# SCH_WL-134A-Carrier-Board_2025-03-29.net
KiCad netlist of a schematic drawn in EasyEDA
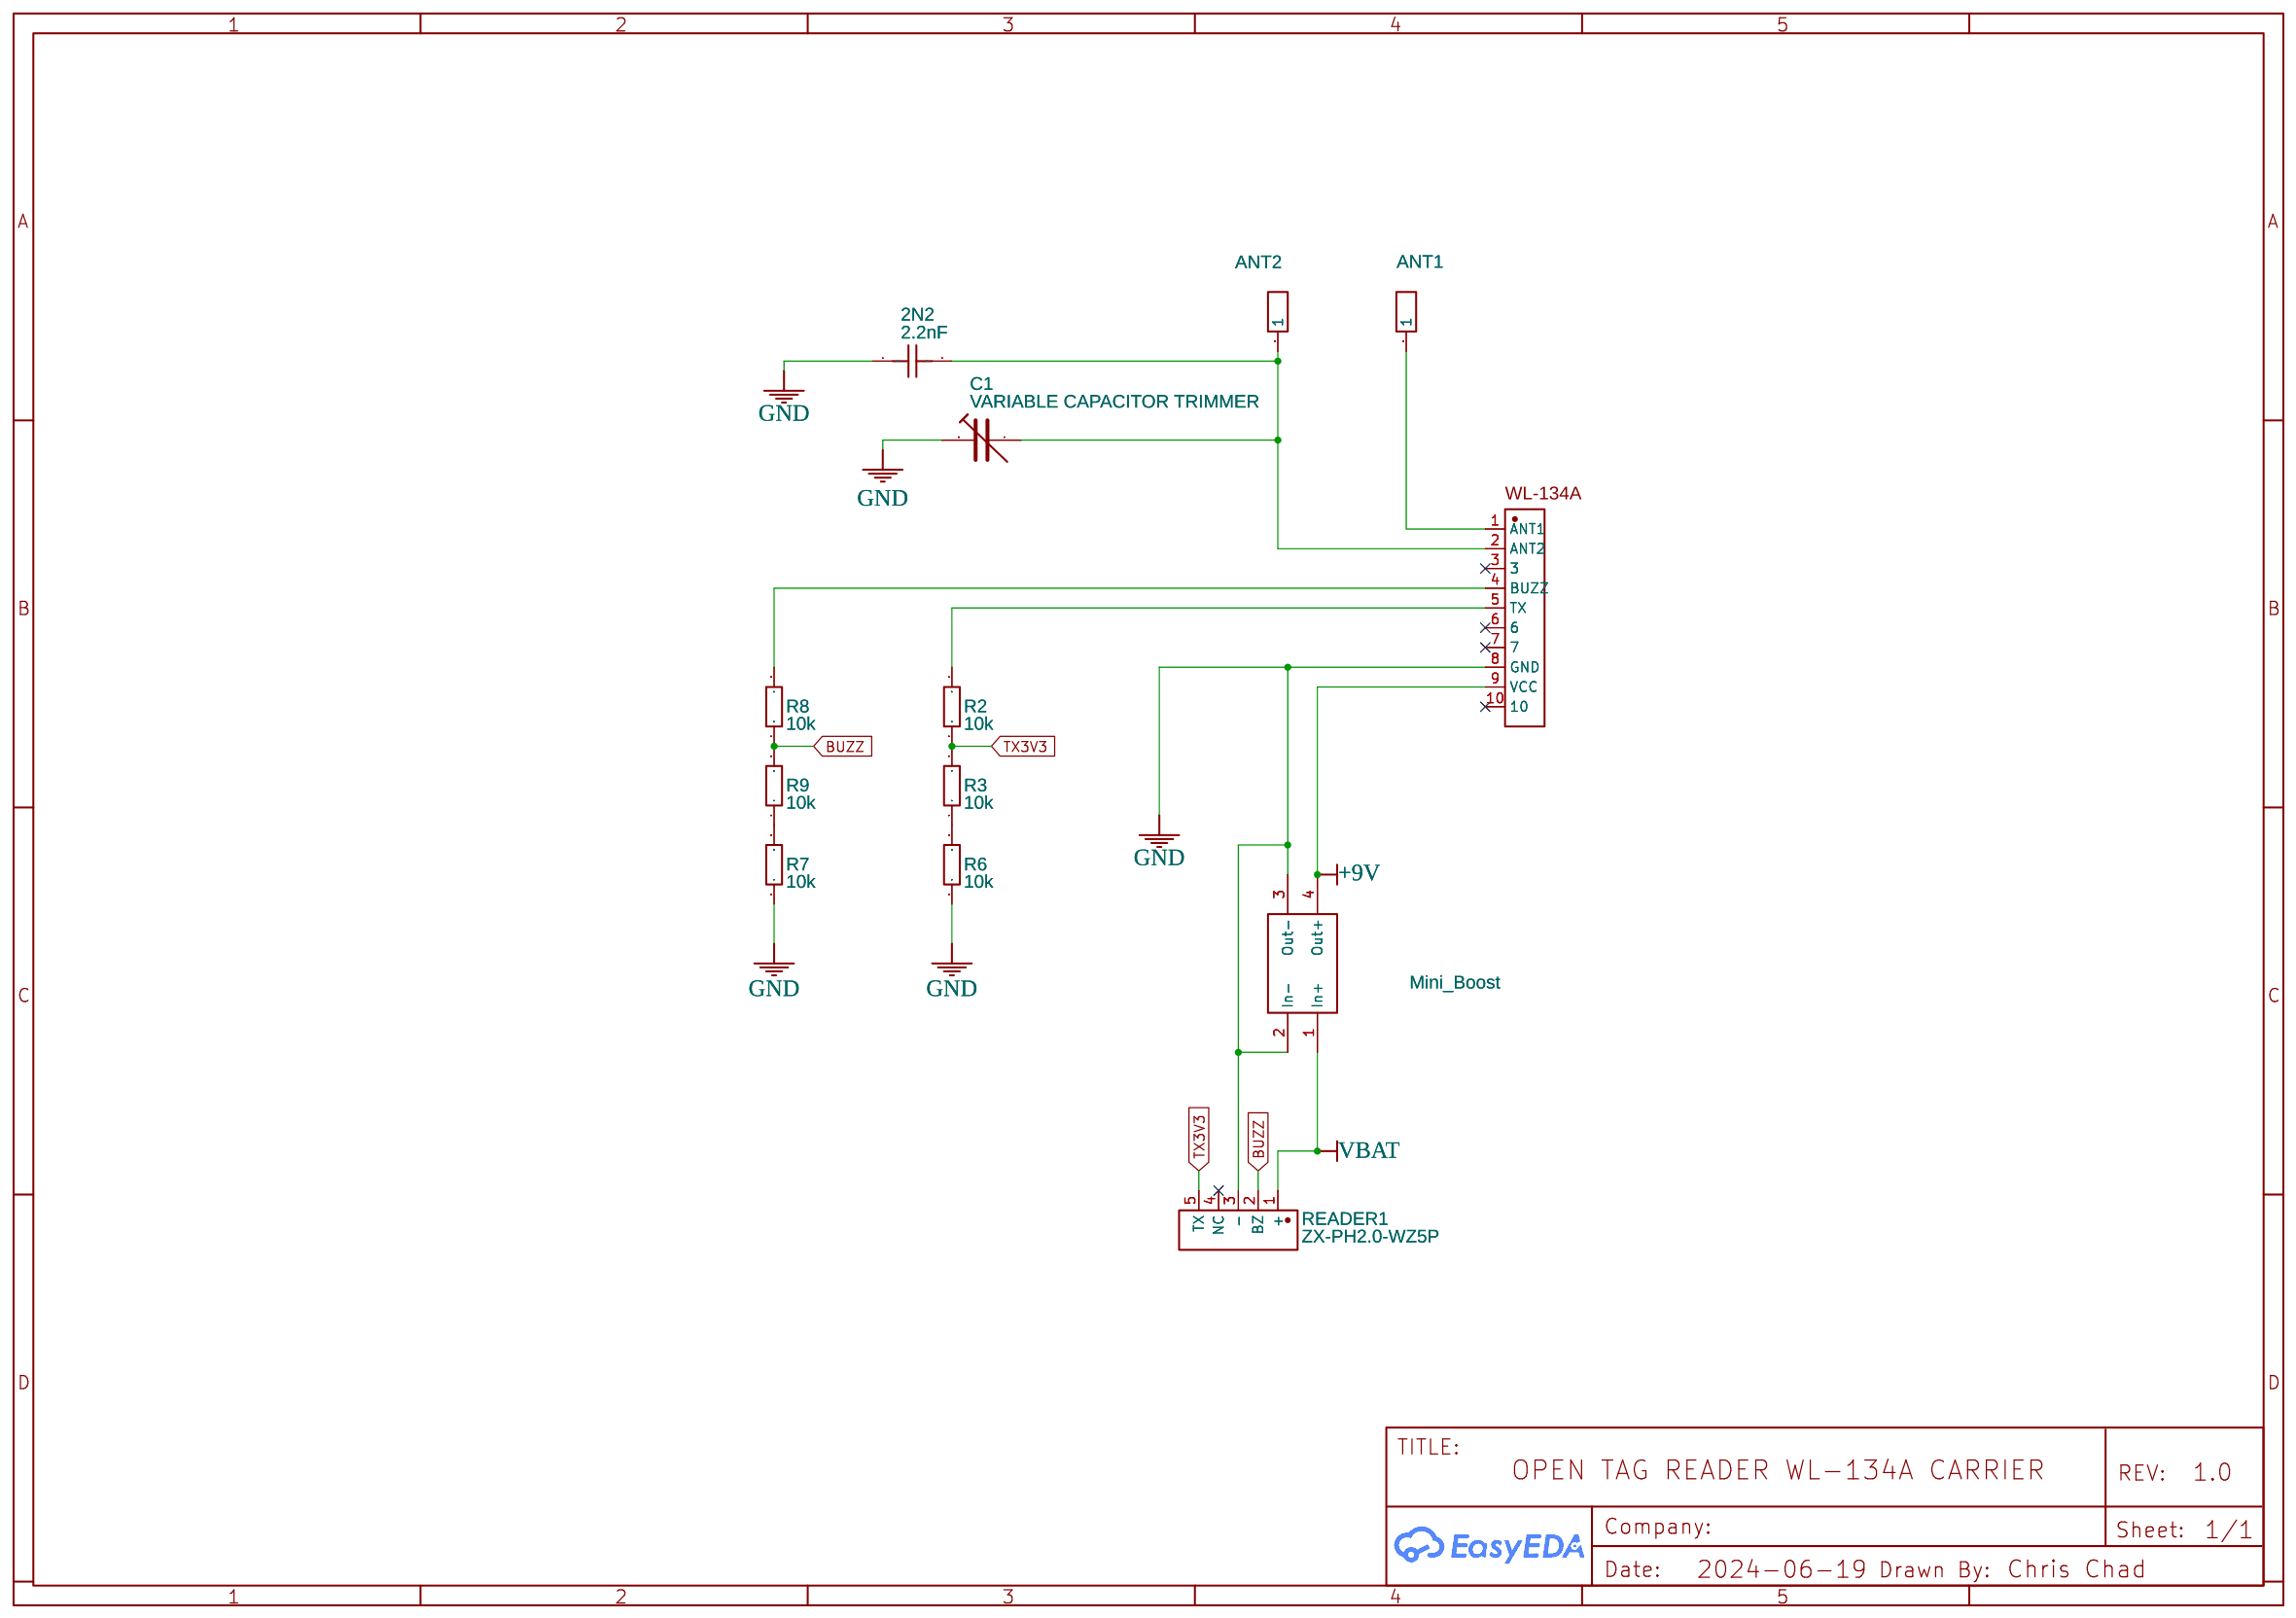
[diagram p0: schematic sheet]

(export (version "E")
  (design (tool "Eeschema 10.0.6"))
  (components
    (comp (ref "2N2")
      (value "2.2nF")
      (fields (field (name "Manufacturer Part") "B32529C8222J189") (field (name "Manufacturer") "TDK"))
      (libsource (lib "") (part "B32529C8222J189"))
    )
    (comp (ref "ANT1") (value "HDR-M-2.54_1x1") (libsource (lib "") (part "HDR-M-2.54_1x1")))
    (comp (ref "ANT2") (value "HDR-M-2.54_1x1") (libsource (lib "") (part "HDR-M-2.54_1x1")))
    (comp (ref "C1")
      (value "VARIABLE CAPACITOR TRIMMER")
      (libsource (lib "") (part "VARIABLE CAPACITOR TRIMMER"))
    )
    (comp (ref "R2")
      (value "10k")
      (fields (field (name "Manufacturer Part") "RT0805DRD07510RL") (field (name "Manufacturer") "YAGEO(国巨)"))
      (libsource (lib "") (part "RT0805DRD07510RL"))
    )
    (comp (ref "R3")
      (value "10k")
      (fields (field (name "Manufacturer Part") "RC0805DR-071KL") (field (name "Manufacturer") "YAGEO(国巨)"))
      (libsource (lib "") (part "RC0805DR-071KL"))
    )
    (comp (ref "R6")
      (value "10k")
      (fields (field (name "Manufacturer Part") "RC0805DR-071KL") (field (name "Manufacturer") "YAGEO(国巨)"))
      (libsource (lib "") (part "RC0805DR-071KL"))
    )
    (comp (ref "R7")
      (value "10k")
      (fields (field (name "Manufacturer Part") "RC0805DR-071KL") (field (name "Manufacturer") "YAGEO(国巨)"))
      (libsource (lib "") (part "RC0805DR-071KL"))
    )
    (comp (ref "R8")
      (value "10k")
      (fields (field (name "Manufacturer Part") "RT0805DRD07510RL") (field (name "Manufacturer") "YAGEO(国巨)"))
      (libsource (lib "") (part "RT0805DRD07510RL"))
    )
    (comp (ref "R9")
      (value "10k")
      (fields (field (name "Manufacturer Part") "RC0805DR-071KL") (field (name "Manufacturer") "YAGEO(国巨)"))
      (libsource (lib "") (part "RC0805DR-071KL"))
    )
    (comp (ref "READER1")
      (value "ZX-PH2.0-WZ5P")
      (fields (field (name "Manufacturer") "Megastar(兆星)"))
      (libsource (lib "") (part "ZX-PH2.0-WZ5P"))
    )
    (comp (ref "U1") (value "WL-134A") (libsource (lib "") (part "WL-134A")))
    (comp (ref "U2") (value "Mini_Boost") (libsource (lib "") (part "Mini_Boost")))
  )
  (nets
    (net (code "1") (name "+9V") (class "Default")
      (node (ref "U1") (pin "9") (pinfunction "VCC_9") (pintype "unspecified"))
      (node (ref "U2") (pin "4") (pinfunction "Out+_4") (pintype "unspecified"))
    )
    (net (code "2") (name "BUZZ") (class "Default")
      (node (ref "R8") (pin "1") (pinfunction "1_1") (pintype "unspecified"))
      (node (ref "R9") (pin "2") (pinfunction "2_2") (pintype "unspecified"))
      (node (ref "READER1") (pin "2") (pinfunction "BZ_2") (pintype "unspecified"))
    )
    (net (code "3") (name "GND") (class "Default")
      (node (ref "2N2") (pin "1") (pinfunction "1_1") (pintype "unspecified"))
      (node (ref "C1") (pin "2") (pintype "unspecified"))
      (node (ref "R6") (pin "1") (pinfunction "1_1") (pintype "unspecified"))
      (node (ref "R7") (pin "1") (pinfunction "1_1") (pintype "unspecified"))
      (node (ref "READER1") (pin "3") (pinfunction "-_3") (pintype "unspecified"))
      (node (ref "U1") (pin "8") (pinfunction "GND_8") (pintype "unspecified"))
      (node (ref "U2") (pin "2") (pinfunction "In-_2") (pintype "unspecified"))
      (node (ref "U2") (pin "3") (pinfunction "Out-_3") (pintype "unspecified"))
    )
    (net (code "4") (name "Net-(R3-Pad1)") (class "Default")
      (node (ref "R3") (pin "1") (pinfunction "1_1") (pintype "unspecified"))
      (node (ref "R6") (pin "2") (pinfunction "2_2") (pintype "unspecified"))
    )
    (net (code "5") (name "Net-(R7-Pad2)") (class "Default")
      (node (ref "R7") (pin "2") (pinfunction "2_2") (pintype "unspecified"))
      (node (ref "R9") (pin "1") (pinfunction "1_1") (pintype "unspecified"))
    )
    (net (code "6") (name "Net-(U1-ANT1)") (class "Default")
      (node (ref "ANT1") (pin "1") (pinfunction "1_1") (pintype "input"))
      (node (ref "U1") (pin "1") (pinfunction "ANT1_1") (pintype "unspecified"))
    )
    (net (code "7") (name "Net-(U1-ANT2)") (class "Default")
      (node (ref "2N2") (pin "2") (pinfunction "2_2") (pintype "unspecified"))
      (node (ref "ANT2") (pin "1") (pinfunction "1_1") (pintype "input"))
      (node (ref "C1") (pin "1") (pintype "unspecified"))
      (node (ref "U1") (pin "2") (pinfunction "ANT2_2") (pintype "unspecified"))
    )
    (net (code "8") (name "Net-(U1-BUZZ)") (class "Default")
      (node (ref "R8") (pin "2") (pinfunction "2_2") (pintype "unspecified"))
      (node (ref "U1") (pin "4") (pinfunction "BUZZ_4") (pintype "unspecified"))
    )
    (net (code "9") (name "Net-(U1-TX)") (class "Default")
      (node (ref "R2") (pin "2") (pinfunction "2_2") (pintype "unspecified"))
      (node (ref "U1") (pin "5") (pinfunction "TX_5") (pintype "unspecified"))
    )
    (net (code "10") (name "TX3V3") (class "Default")
      (node (ref "R2") (pin "1") (pinfunction "1_1") (pintype "unspecified"))
      (node (ref "R3") (pin "2") (pinfunction "2_2") (pintype "unspecified"))
      (node (ref "READER1") (pin "5") (pinfunction "TX_5") (pintype "unspecified"))
    )
    (net (code "11") (name "VBAT") (class "Default")
      (node (ref "READER1") (pin "1") (pinfunction "+_1") (pintype "unspecified"))
      (node (ref "U2") (pin "1") (pinfunction "In+_1") (pintype "unspecified"))
    )
    (net (code "12") (name "unconnected-(READER1-NC-Pad4)") (class "Default")
      (node (ref "READER1") (pin "4") (pinfunction "NC_4") (pintype "unspecified+no_connect"))
    )
    (net (code "13") (name "unconnected-(U1-Pad3)") (class "Default")
      (node (ref "U1") (pin "3") (pinfunction "3_3") (pintype "unspecified+no_connect"))
    )
    (net (code "14") (name "unconnected-(U1-Pad6)") (class "Default")
      (node (ref "U1") (pin "6") (pinfunction "6_6") (pintype "unspecified+no_connect"))
    )
    (net (code "15") (name "unconnected-(U1-Pad7)") (class "Default")
      (node (ref "U1") (pin "7") (pinfunction "7_7") (pintype "unspecified+no_connect"))
    )
    (net (code "16") (name "unconnected-(U1-Pad10)") (class "Default")
      (node (ref "U1") (pin "10") (pinfunction "10_10") (pintype "unspecified+no_connect"))
    )
  )
)
